# Sheet1.net
KiCad netlist of a schematic drawn in Altium Designer
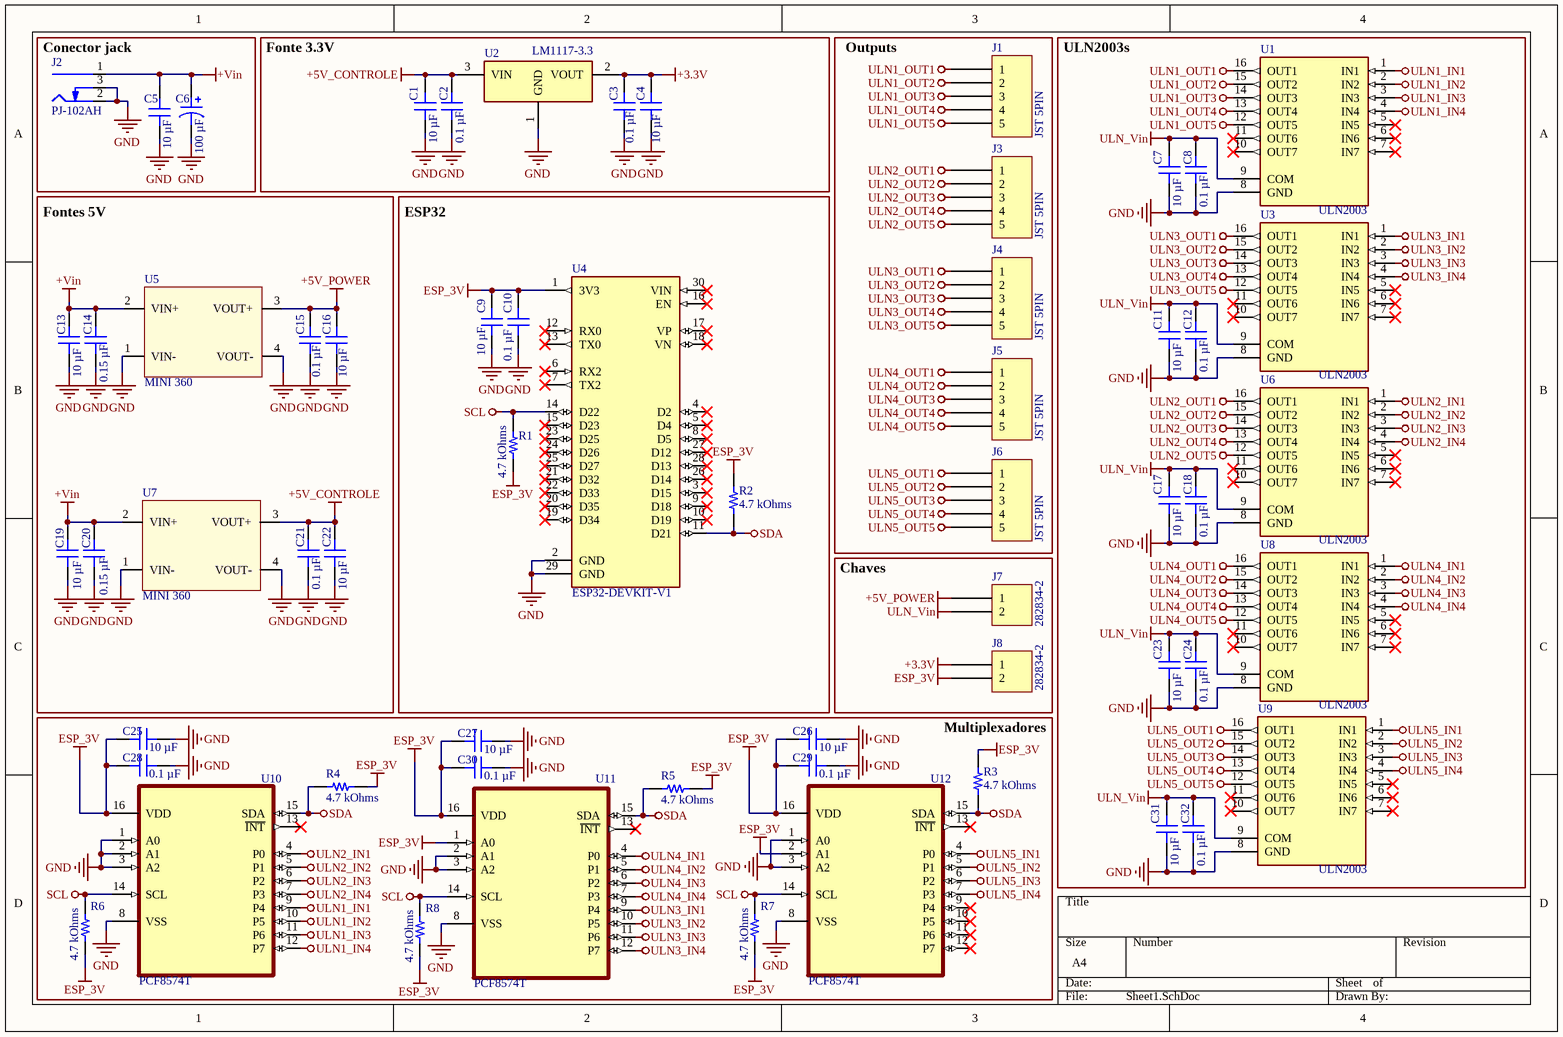
[diagram p0: Sheet1.SchDoc]

(export (version "E")
  (design (tool "Eeschema 10.0.6"))
  (components
    (comp (ref "C1")
      (value "10 µF")
      (footprint "CAP 0603_1608")
      (description "CAP CER 10UF 6.3V X5R 0603")
      (fields
        (field (name "PART NUMBER") "GRM188R60J106ME47D")
        (field (name "CAPACITANCE") "10 µF")
        (field (name "MANUFACTURER") "Murata Electronics")
      )
      (libsource (lib "Celestial Altium Library - altium_library") (part "Capacitor"))
    )
    (comp (ref "C2")
      (value "0.1 µF")
      (footprint "CAP 0603_1608")
      (description "CAP CER 0.1UF 6.3V X7R 0603")
      (fields
        (field (name "PART NUMBER") "6R3X14W104MV4T")
        (field (name "CAPACITANCE") "0.1 µF")
        (field (name "MANUFACTURER") "Johanson Dielectrics Inc.")
      )
      (libsource (lib "Celestial Altium Library - altium_library") (part "Capacitor"))
    )
    (comp (ref "C3")
      (value "0.1 µF")
      (footprint "CAP 0603_1608")
      (description "CAP CER 0.1UF 6.3V X7R 0603")
      (fields
        (field (name "PART NUMBER") "6R3X14W104MV4T")
        (field (name "CAPACITANCE") "0.1 µF")
        (field (name "MANUFACTURER") "Johanson Dielectrics Inc.")
      )
      (libsource (lib "Celestial Altium Library - altium_library") (part "Capacitor"))
    )
    (comp (ref "C4")
      (value "10 µF")
      (footprint "CAP 0603_1608")
      (description "CAP CER 10UF 6.3V X5R 0603")
      (fields
        (field (name "PART NUMBER") "GRM188R60J106ME47D")
        (field (name "CAPACITANCE") "10 µF")
        (field (name "MANUFACTURER") "Murata Electronics")
      )
      (libsource (lib "Celestial Altium Library - altium_library") (part "Capacitor"))
    )
    (comp (ref "C5")
      (value "10 µF")
      (footprint "CAP 1206_3216 - 0.8MM")
      (description "CAP CER 10UF 16V X5R 1206")
      (fields
        (field (name "PART NUMBER") "EMK316BJ106MD-T")
        (field (name "CAPACITANCE") "10 µF")
        (field (name "MANUFACTURER") "Taiyo Yuden")
      )
      (libsource (lib "Celestial Altium Library - altium_library") (part "Capacitor"))
    )
    (comp (ref "C6")
      (value "100 µF")
      (footprint "CAP AL TH D8 L3.5 H12.5")
      (description "CAP ALUM 100UF 20% 16V RADIAL")
      (fields (field (name "PART NUMBER") "UKL1C101MPD1TD") (field (name "MANUFACTURER") "Nichicon"))
      (libsource (lib "Celestial Altium Library - altium_library") (part "Polarised Capacitor"))
    )
    (comp (ref "C7")
      (value "10 µF")
      (footprint "CAP 0603_1608")
      (description "CAP CER 10UF 6.3V X5R 0603")
      (fields
        (field (name "PART NUMBER") "GRM188R60J106ME47D")
        (field (name "CAPACITANCE") "10 µF")
        (field (name "MANUFACTURER") "Murata Electronics")
      )
      (libsource (lib "Celestial Altium Library - altium_library") (part "Capacitor"))
    )
    (comp (ref "C8")
      (value "0.1 µF")
      (footprint "CAP 0603_1608")
      (description "CAP CER 0.1UF 6.3V X7R 0603")
      (fields
        (field (name "PART NUMBER") "6R3X14W104MV4T")
        (field (name "CAPACITANCE") "0.1 µF")
        (field (name "MANUFACTURER") "Johanson Dielectrics Inc.")
      )
      (libsource (lib "Celestial Altium Library - altium_library") (part "Capacitor"))
    )
    (comp (ref "C9")
      (value "10 µF")
      (footprint "CAP 0603_1608")
      (description "CAP CER 10UF 6.3V X5R 0603")
      (fields
        (field (name "PART NUMBER") "GRM188R60J106ME47D")
        (field (name "CAPACITANCE") "10 µF")
        (field (name "MANUFACTURER") "Murata Electronics")
      )
      (libsource (lib "Celestial Altium Library - altium_library") (part "Capacitor"))
    )
    (comp (ref "C10")
      (value "0.1 µF")
      (footprint "CAP 0603_1608")
      (description "CAP CER 0.1UF 6.3V X7R 0603")
      (fields
        (field (name "PART NUMBER") "6R3X14W104MV4T")
        (field (name "CAPACITANCE") "0.1 µF")
        (field (name "MANUFACTURER") "Johanson Dielectrics Inc.")
      )
      (libsource (lib "Celestial Altium Library - altium_library") (part "Capacitor"))
    )
    (comp (ref "C11")
      (value "10 µF")
      (footprint "CAP 0603_1608")
      (description "CAP CER 10UF 6.3V X5R 0603")
      (fields
        (field (name "PART NUMBER") "GRM188R60J106ME47D")
        (field (name "CAPACITANCE") "10 µF")
        (field (name "MANUFACTURER") "Murata Electronics")
      )
      (libsource (lib "Celestial Altium Library - altium_library") (part "Capacitor"))
    )
    (comp (ref "C12")
      (value "0.1 µF")
      (footprint "CAP 0603_1608")
      (description "CAP CER 0.1UF 6.3V X7R 0603")
      (fields
        (field (name "PART NUMBER") "6R3X14W104MV4T")
        (field (name "CAPACITANCE") "0.1 µF")
        (field (name "MANUFACTURER") "Johanson Dielectrics Inc.")
      )
      (libsource (lib "Celestial Altium Library - altium_library") (part "Capacitor"))
    )
    (comp (ref "C13")
      (value "10 µF")
      (footprint "CAP 1206_3216 - 0.8MM")
      (description "CAP CER 10UF 16V X5R 1206")
      (fields
        (field (name "PART NUMBER") "EMK316BJ106MD-T")
        (field (name "CAPACITANCE") "10 µF")
        (field (name "MANUFACTURER") "Taiyo Yuden")
      )
      (libsource (lib "Celestial Altium Library - altium_library") (part "Capacitor"))
    )
    (comp (ref "C14")
      (value "0.15 µF")
      (footprint "CAP 0805_2012")
      (description "CAP CER 0.15UF 50V X7R 0805")
      (fields
        (field (name "PART NUMBER") "C0805C154K5RACAUTO")
        (field (name "CAPACITANCE") "0.15 µF")
        (field (name "MANUFACTURER") "KEMET")
      )
      (libsource (lib "Celestial Altium Library - altium_library") (part "Capacitor"))
    )
    (comp (ref "C15")
      (value "0.1 µF")
      (footprint "CAP 0603_1608")
      (description "CAP CER 0.1UF 6.3V X7R 0603")
      (fields
        (field (name "PART NUMBER") "6R3X14W104MV4T")
        (field (name "CAPACITANCE") "0.1 µF")
        (field (name "MANUFACTURER") "Johanson Dielectrics Inc.")
      )
      (libsource (lib "Celestial Altium Library - altium_library") (part "Capacitor"))
    )
    (comp (ref "C16")
      (value "10 µF")
      (footprint "CAP 0603_1608")
      (description "CAP CER 10UF 6.3V X5R 0603")
      (fields
        (field (name "PART NUMBER") "GRM188R60J106ME47D")
        (field (name "CAPACITANCE") "10 µF")
        (field (name "MANUFACTURER") "Murata Electronics")
      )
      (libsource (lib "Celestial Altium Library - altium_library") (part "Capacitor"))
    )
    (comp (ref "C17")
      (value "10 µF")
      (footprint "CAP 0603_1608")
      (description "CAP CER 10UF 6.3V X5R 0603")
      (fields
        (field (name "PART NUMBER") "GRM188R60J106ME47D")
        (field (name "CAPACITANCE") "10 µF")
        (field (name "MANUFACTURER") "Murata Electronics")
      )
      (libsource (lib "Celestial Altium Library - altium_library") (part "Capacitor"))
    )
    (comp (ref "C18")
      (value "0.1 µF")
      (footprint "CAP 0603_1608")
      (description "CAP CER 0.1UF 6.3V X7R 0603")
      (fields
        (field (name "PART NUMBER") "6R3X14W104MV4T")
        (field (name "CAPACITANCE") "0.1 µF")
        (field (name "MANUFACTURER") "Johanson Dielectrics Inc.")
      )
      (libsource (lib "Celestial Altium Library - altium_library") (part "Capacitor"))
    )
    (comp (ref "C19")
      (value "10 µF")
      (footprint "CAP 1206_3216 - 0.8MM")
      (description "CAP CER 10UF 16V X5R 1206")
      (fields
        (field (name "PART NUMBER") "EMK316BJ106MD-T")
        (field (name "CAPACITANCE") "10 µF")
        (field (name "MANUFACTURER") "Taiyo Yuden")
      )
      (libsource (lib "Celestial Altium Library - altium_library") (part "Capacitor"))
    )
    (comp (ref "C20")
      (value "0.15 µF")
      (footprint "CAP 0805_2012")
      (description "CAP CER 0.15UF 50V X7R 0805")
      (fields
        (field (name "PART NUMBER") "C0805C154K5RACAUTO")
        (field (name "CAPACITANCE") "0.15 µF")
        (field (name "MANUFACTURER") "KEMET")
      )
      (libsource (lib "Celestial Altium Library - altium_library") (part "Capacitor"))
    )
    (comp (ref "C21")
      (value "0.1 µF")
      (footprint "CAP 0603_1608")
      (description "CAP CER 0.1UF 6.3V X7R 0603")
      (fields
        (field (name "PART NUMBER") "6R3X14W104MV4T")
        (field (name "CAPACITANCE") "0.1 µF")
        (field (name "MANUFACTURER") "Johanson Dielectrics Inc.")
      )
      (libsource (lib "Celestial Altium Library - altium_library") (part "Capacitor"))
    )
    (comp (ref "C22")
      (value "10 µF")
      (footprint "CAP 0603_1608")
      (description "CAP CER 10UF 6.3V X5R 0603")
      (fields
        (field (name "PART NUMBER") "GRM188R60J106ME47D")
        (field (name "CAPACITANCE") "10 µF")
        (field (name "MANUFACTURER") "Murata Electronics")
      )
      (libsource (lib "Celestial Altium Library - altium_library") (part "Capacitor"))
    )
    (comp (ref "C23")
      (value "10 µF")
      (footprint "CAP 0603_1608")
      (description "CAP CER 10UF 6.3V X5R 0603")
      (fields
        (field (name "PART NUMBER") "GRM188R60J106ME47D")
        (field (name "CAPACITANCE") "10 µF")
        (field (name "MANUFACTURER") "Murata Electronics")
      )
      (libsource (lib "Celestial Altium Library - altium_library") (part "Capacitor"))
    )
    (comp (ref "C24")
      (value "0.1 µF")
      (footprint "CAP 0603_1608")
      (description "CAP CER 0.1UF 6.3V X7R 0603")
      (fields
        (field (name "PART NUMBER") "6R3X14W104MV4T")
        (field (name "CAPACITANCE") "0.1 µF")
        (field (name "MANUFACTURER") "Johanson Dielectrics Inc.")
      )
      (libsource (lib "Celestial Altium Library - altium_library") (part "Capacitor"))
    )
    (comp (ref "C25")
      (value "10 µF")
      (footprint "CAP 0603_1608")
      (description "CAP CER 10UF 6.3V X5R 0603")
      (fields
        (field (name "PART NUMBER") "GRM188R60J106ME47D")
        (field (name "CAPACITANCE") "10 µF")
        (field (name "MANUFACTURER") "Murata Electronics")
      )
      (libsource (lib "Celestial Altium Library - altium_library") (part "Capacitor"))
    )
    (comp (ref "C26")
      (value "10 µF")
      (footprint "CAP 0603_1608")
      (description "CAP CER 10UF 6.3V X5R 0603")
      (fields
        (field (name "PART NUMBER") "GRM188R60J106ME47D")
        (field (name "CAPACITANCE") "10 µF")
        (field (name "MANUFACTURER") "Murata Electronics")
      )
      (libsource (lib "Celestial Altium Library - altium_library") (part "Capacitor"))
    )
    (comp (ref "C27")
      (value "10 µF")
      (footprint "CAP 0603_1608")
      (description "CAP CER 10UF 6.3V X5R 0603")
      (fields
        (field (name "PART NUMBER") "GRM188R60J106ME47D")
        (field (name "CAPACITANCE") "10 µF")
        (field (name "MANUFACTURER") "Murata Electronics")
      )
      (libsource (lib "Celestial Altium Library - altium_library") (part "Capacitor"))
    )
    (comp (ref "C28")
      (value "0.1 µF")
      (footprint "CAP 0603_1608")
      (description "CAP CER 0.1UF 6.3V X7R 0603")
      (fields
        (field (name "PART NUMBER") "6R3X14W104MV4T")
        (field (name "CAPACITANCE") "0.1 µF")
        (field (name "MANUFACTURER") "Johanson Dielectrics Inc.")
      )
      (libsource (lib "Celestial Altium Library - altium_library") (part "Capacitor"))
    )
    (comp (ref "C29")
      (value "0.1 µF")
      (footprint "CAP 0603_1608")
      (description "CAP CER 0.1UF 6.3V X7R 0603")
      (fields
        (field (name "PART NUMBER") "6R3X14W104MV4T")
        (field (name "CAPACITANCE") "0.1 µF")
        (field (name "MANUFACTURER") "Johanson Dielectrics Inc.")
      )
      (libsource (lib "Celestial Altium Library - altium_library") (part "Capacitor"))
    )
    (comp (ref "C30")
      (value "0.1 µF")
      (footprint "CAP 0603_1608")
      (description "CAP CER 0.1UF 6.3V X7R 0603")
      (fields
        (field (name "PART NUMBER") "6R3X14W104MV4T")
        (field (name "CAPACITANCE") "0.1 µF")
        (field (name "MANUFACTURER") "Johanson Dielectrics Inc.")
      )
      (libsource (lib "Celestial Altium Library - altium_library") (part "Capacitor"))
    )
    (comp (ref "C31")
      (value "10 µF")
      (footprint "CAP 0603_1608")
      (description "CAP CER 10UF 6.3V X5R 0603")
      (fields
        (field (name "PART NUMBER") "GRM188R60J106ME47D")
        (field (name "CAPACITANCE") "10 µF")
        (field (name "MANUFACTURER") "Murata Electronics")
      )
      (libsource (lib "Celestial Altium Library - altium_library") (part "Capacitor"))
    )
    (comp (ref "C32")
      (value "0.1 µF")
      (footprint "CAP 0603_1608")
      (description "CAP CER 0.1UF 6.3V X7R 0603")
      (fields
        (field (name "PART NUMBER") "6R3X14W104MV4T")
        (field (name "CAPACITANCE") "0.1 µF")
        (field (name "MANUFACTURER") "Johanson Dielectrics Inc.")
      )
      (libsource (lib "Celestial Altium Library - altium_library") (part "Capacitor"))
    )
    (comp (ref "J1")
      (value "JST 5PIN")
      (footprint "JST XH B5B-XH-A")
      (description "CONN HEADER VERT 5POS 2.5MM")
      (fields
        (field (name "PART NUMBER") "B5B-XH-A(LF)(SN)")
        (field (name "MANUFACTURER") "JST Sales America Inc.")
      )
      (libsource (lib "Celestial Altium Library - altium_library") (part "5 Pin"))
    )
    (comp (ref "J2")
      (value "PJ-102AH")
      (footprint "CUI PJ-102AH")
      (description "CONN PWR JACK 2X5.5MM SOLDER")
      (fields (field (name "MANUFACTURER") "CUI Devices"))
      (libsource (lib "Celestial Altium Library - altium_library") (part "Barrel Connector"))
    )
    (comp (ref "J3")
      (value "JST 5PIN")
      (footprint "JST XH B5B-XH-A")
      (description "CONN HEADER VERT 5POS 2.5MM")
      (fields
        (field (name "PART NUMBER") "B5B-XH-A(LF)(SN)")
        (field (name "MANUFACTURER") "JST Sales America Inc.")
      )
      (libsource (lib "Celestial Altium Library - altium_library") (part "5 Pin"))
    )
    (comp (ref "J4")
      (value "JST 5PIN")
      (footprint "JST XH B5B-XH-A")
      (description "CONN HEADER VERT 5POS 2.5MM")
      (fields
        (field (name "PART NUMBER") "B5B-XH-A(LF)(SN)")
        (field (name "MANUFACTURER") "JST Sales America Inc.")
      )
      (libsource (lib "Celestial Altium Library - altium_library") (part "5 Pin"))
    )
    (comp (ref "J5")
      (value "JST 5PIN")
      (footprint "JST XH B5B-XH-A")
      (description "CONN HEADER VERT 5POS 2.5MM")
      (fields
        (field (name "PART NUMBER") "B5B-XH-A(LF)(SN)")
        (field (name "MANUFACTURER") "JST Sales America Inc.")
      )
      (libsource (lib "Celestial Altium Library - altium_library") (part "5 Pin"))
    )
    (comp (ref "J6")
      (value "JST 5PIN")
      (footprint "JST XH B5B-XH-A")
      (description "CONN HEADER VERT 5POS 2.5MM")
      (fields
        (field (name "PART NUMBER") "B5B-XH-A(LF)(SN)")
        (field (name "MANUFACTURER") "JST Sales America Inc.")
      )
      (libsource (lib "Celestial Altium Library - altium_library") (part "5 Pin"))
    )
    (comp (ref "J7")
      (value "282834-2")
      (footprint "TE 282834-2")
      (description "TERM BLK 2P SIDE ENT 2.54MM PCB")
      (fields (field (name "MANUFACTURER") "TE Connectivity AMP Connectors") (field (name "VOLTAGE") "150V"))
      (libsource (lib "Celestial Altium Library - altium_library") (part "2 Pin"))
    )
    (comp (ref "J8")
      (value "282834-2")
      (footprint "TE 282834-2")
      (description "TERM BLK 2P SIDE ENT 2.54MM PCB")
      (fields (field (name "MANUFACTURER") "TE Connectivity AMP Connectors") (field (name "VOLTAGE") "150V"))
      (libsource (lib "Celestial Altium Library - altium_library") (part "2 Pin"))
    )
    (comp (ref "R1")
      (value "4.7 kOhms")
      (footprint "RES 0603_1608")
      (description "RES SMD 4.7K OHM 1% 1/10W 0603")
      (fields (field (name "PART NUMBER") "RT0603FRE074K7L") (field (name "MANUFACTURER") "Yageo"))
      (libsource (lib "Celestial Altium Library - altium_library") (part "Resistor"))
    )
    (comp (ref "R2")
      (value "4.7 kOhms")
      (footprint "RES 0603_1608")
      (description "RES SMD 4.7K OHM 1% 1/10W 0603")
      (fields (field (name "PART NUMBER") "RT0603FRE074K7L") (field (name "MANUFACTURER") "Yageo"))
      (libsource (lib "Celestial Altium Library - altium_library") (part "Resistor"))
    )
    (comp (ref "R3")
      (value "4.7 kOhms")
      (footprint "RES 0603_1608")
      (description "RES SMD 4.7K OHM 1% 1/10W 0603")
      (fields (field (name "PART NUMBER") "RT0603FRE074K7L") (field (name "MANUFACTURER") "Yageo"))
      (libsource (lib "Celestial Altium Library - altium_library") (part "Resistor"))
    )
    (comp (ref "R4")
      (value "4.7 kOhms")
      (footprint "RES 0603_1608")
      (description "RES SMD 4.7K OHM 1% 1/10W 0603")
      (fields (field (name "PART NUMBER") "RT0603FRE074K7L") (field (name "MANUFACTURER") "Yageo"))
      (libsource (lib "Celestial Altium Library - altium_library") (part "Resistor"))
    )
    (comp (ref "R5")
      (value "4.7 kOhms")
      (footprint "RES 0603_1608")
      (description "RES SMD 4.7K OHM 1% 1/10W 0603")
      (fields (field (name "PART NUMBER") "RT0603FRE074K7L") (field (name "MANUFACTURER") "Yageo"))
      (libsource (lib "Celestial Altium Library - altium_library") (part "Resistor"))
    )
    (comp (ref "R6")
      (value "4.7 kOhms")
      (footprint "RES 0603_1608")
      (description "RES SMD 4.7K OHM 1% 1/10W 0603")
      (fields (field (name "PART NUMBER") "RT0603FRE074K7L") (field (name "MANUFACTURER") "Yageo"))
      (libsource (lib "Celestial Altium Library - altium_library") (part "Resistor"))
    )
    (comp (ref "R7")
      (value "4.7 kOhms")
      (footprint "RES 0603_1608")
      (description "RES SMD 4.7K OHM 1% 1/10W 0603")
      (fields (field (name "PART NUMBER") "RT0603FRE074K7L") (field (name "MANUFACTURER") "Yageo"))
      (libsource (lib "Celestial Altium Library - altium_library") (part "Resistor"))
    )
    (comp (ref "R8")
      (value "4.7 kOhms")
      (footprint "RES 0603_1608")
      (description "RES SMD 4.7K OHM 1% 1/10W 0603")
      (fields (field (name "PART NUMBER") "RT0603FRE074K7L") (field (name "MANUFACTURER") "Yageo"))
      (libsource (lib "Celestial Altium Library - altium_library") (part "Resistor"))
    )
    (comp (ref "U1")
      (value "ULN2003")
      (footprint "DIP762W46P254L1969H533Q16")
      (description "Bipolar (BJT) Transistor Array 7 NPN Darlington 50V 500mA - - Surface Mount 16-SOIC")
      (fields (field (name "MF") "Texas Instruments"))
      (libsource (lib "ULN2003") (part "ULN2003"))
    )
    (comp (ref "U2")
      (value "LM1117-3.3")
      (footprint "SOT-223")
      (description "Linear Voltage Regulator IC Positive Fixed 1 Output 800mA DDPAK/TO-263-3")
      (fields (field (name "MF") "Texas Instruments"))
      (libsource (lib "LM1117-3.3") (part "LM1117-3.3"))
    )
    (comp (ref "U3")
      (value "ULN2003")
      (footprint "DIP762W46P254L1969H533Q16")
      (description "Bipolar (BJT) Transistor Array 7 NPN Darlington 50V 500mA - - Surface Mount 16-SOIC")
      (fields (field (name "MF") "Texas Instruments"))
      (libsource (lib "ULN2003") (part "ULN2003"))
    )
    (comp (ref "U4")
      (value "ESP32-DEVKIT-V1")
      (footprint "MODULE_ESP32_DEVKIT_V1")
      (fields (field (name "MF") "Do it"))
      (libsource (lib "ESP32-DEVKIT-V1") (part "ESP32-DEVKIT-V1"))
    )
    (comp (ref "U5")
      (value "MINI 360")
      (footprint "MINI360")
      (libsource (lib "bibliotecamini360") (part "MINI 360"))
    )
    (comp (ref "U6")
      (value "ULN2003")
      (footprint "DIP762W46P254L1969H533Q16")
      (description "Bipolar (BJT) Transistor Array 7 NPN Darlington 50V 500mA - - Surface Mount 16-SOIC")
      (fields (field (name "MF") "Texas Instruments"))
      (libsource (lib "ULN2003") (part "ULN2003"))
    )
    (comp (ref "U7")
      (value "MINI 360")
      (footprint "MINI360")
      (libsource (lib "bibliotecamini360") (part "MINI 360"))
    )
    (comp (ref "U8")
      (value "ULN2003")
      (footprint "DIP762W46P254L1969H533Q16")
      (description "Bipolar (BJT) Transistor Array 7 NPN Darlington 50V 500mA - - Surface Mount 16-SOIC")
      (fields (field (name "MF") "Texas Instruments"))
      (libsource (lib "ULN2003") (part "ULN2003"))
    )
    (comp (ref "U9")
      (value "ULN2003")
      (footprint "DIP762W46P254L1969H533Q16")
      (description "Bipolar (BJT) Transistor Array 7 NPN Darlington 50V 500mA - - Surface Mount 16-SOIC")
      (fields (field (name "MF") "Texas Instruments"))
      (libsource (lib "ULN2003") (part "ULN2003"))
    )
    (comp (ref "U10")
      (value "PCF8574T")
      (footprint "SOIC127P1032X265-16N")
      (description "I/O Expander 8 IÂ²C 100 kHz 20-SSOP")
      (fields (field (name "MF") "NXP Semiconductors"))
      (libsource (lib "PCF8574T") (part "PCF8574T"))
    )
    (comp (ref "U11")
      (value "PCF8574T")
      (footprint "SOIC127P1032X265-16N")
      (description "I/O Expander 8 IÂ²C 100 kHz 20-SSOP")
      (fields (field (name "MF") "NXP Semiconductors"))
      (libsource (lib "PCF8574T") (part "PCF8574T"))
    )
    (comp (ref "U12")
      (value "PCF8574T")
      (footprint "SOIC127P1032X265-16N")
      (description "I/O Expander 8 IÂ²C 100 kHz 20-SSOP")
      (fields (field (name "MF") "NXP Semiconductors"))
      (libsource (lib "PCF8574T") (part "PCF8574T"))
    )
  )
  (nets
    (net (code "1") (name "+3.3V") (class "Default")
      (node (ref "C3") (pin "1") (pinfunction "1_1") (pintype "passive"))
      (node (ref "C4") (pin "1") (pinfunction "1_1") (pintype "passive"))
      (node (ref "J8") (pin "1") (pinfunction "1_1") (pintype "passive"))
      (node (ref "U2") (pin "2") (pinfunction "VOUT_2") (pintype "passive"))
    )
    (net (code "2") (name "+5V_CONTROLE") (class "Default")
      (node (ref "C1") (pin "1") (pinfunction "1_1") (pintype "passive"))
      (node (ref "C2") (pin "1") (pinfunction "1_1") (pintype "passive"))
      (node (ref "C21") (pin "1") (pinfunction "1_1") (pintype "passive"))
      (node (ref "C22") (pin "1") (pinfunction "1_1") (pintype "passive"))
      (node (ref "U2") (pin "3") (pinfunction "VIN_3") (pintype "passive"))
      (node (ref "U7") (pin "3") (pinfunction "VOUT+_3") (pintype "passive"))
    )
    (net (code "3") (name "+5V_POWER") (class "Default")
      (node (ref "C15") (pin "1") (pinfunction "1_1") (pintype "passive"))
      (node (ref "C16") (pin "1") (pinfunction "1_1") (pintype "passive"))
      (node (ref "J7") (pin "1") (pinfunction "1_1") (pintype "passive"))
      (node (ref "U5") (pin "3") (pinfunction "VOUT+_3") (pintype "passive"))
    )
    (net (code "4") (name "+Vin") (class "Default")
      (node (ref "C13") (pin "1") (pinfunction "1_1") (pintype "passive"))
      (node (ref "C14") (pin "2") (pinfunction "2_2") (pintype "passive"))
      (node (ref "C19") (pin "1") (pinfunction "1_1") (pintype "passive"))
      (node (ref "C20") (pin "2") (pinfunction "2_2") (pintype "passive"))
      (node (ref "C5") (pin "1") (pinfunction "1_1") (pintype "passive"))
      (node (ref "C6") (pin "1") (pinfunction "1_1") (pintype "passive"))
      (node (ref "J2") (pin "1") (pinfunction "Centre_1") (pintype "passive"))
      (node (ref "U5") (pin "2") (pinfunction "VIN+_2") (pintype "passive"))
      (node (ref "U7") (pin "2") (pinfunction "VIN+_2") (pintype "passive"))
    )
    (net (code "5") (name "ESP_3V") (class "Default")
      (node (ref "C10") (pin "1") (pinfunction "1_1") (pintype "passive"))
      (node (ref "C25") (pin "1") (pinfunction "1_1") (pintype "passive"))
      (node (ref "C26") (pin "1") (pinfunction "1_1") (pintype "passive"))
      (node (ref "C27") (pin "1") (pinfunction "1_1") (pintype "passive"))
      (node (ref "C28") (pin "1") (pinfunction "1_1") (pintype "passive"))
      (node (ref "C29") (pin "1") (pinfunction "1_1") (pintype "passive"))
      (node (ref "C30") (pin "1") (pinfunction "1_1") (pintype "passive"))
      (node (ref "C9") (pin "1") (pinfunction "1_1") (pintype "passive"))
      (node (ref "J8") (pin "2") (pinfunction "2_2") (pintype "passive"))
      (node (ref "R1") (pin "2") (pinfunction "2_2") (pintype "passive"))
      (node (ref "R2") (pin "2") (pinfunction "2_2") (pintype "passive"))
      (node (ref "R3") (pin "2") (pinfunction "2_2") (pintype "passive"))
      (node (ref "R4") (pin "2") (pinfunction "2_2") (pintype "passive"))
      (node (ref "R5") (pin "2") (pinfunction "2_2") (pintype "passive"))
      (node (ref "R6") (pin "2") (pinfunction "2_2") (pintype "passive"))
      (node (ref "R7") (pin "2") (pinfunction "2_2") (pintype "passive"))
      (node (ref "R8") (pin "2") (pinfunction "2_2") (pintype "passive"))
      (node (ref "U10") (pin "16") (pinfunction "VDD_16") (pintype "power_in"))
      (node (ref "U11") (pin "1") (pinfunction "A0_1") (pintype "input"))
      (node (ref "U11") (pin "16") (pinfunction "VDD_16") (pintype "power_in"))
      (node (ref "U12") (pin "16") (pinfunction "VDD_16") (pintype "power_in"))
      (node (ref "U12") (pin "2") (pinfunction "A1_2") (pintype "input"))
      (node (ref "U4") (pin "1") (pinfunction "3V3_1") (pintype "output"))
    )
    (net (code "6") (name "GND") (class "Default")
      (node (ref "C1") (pin "2") (pinfunction "2_2") (pintype "passive"))
      (node (ref "C10") (pin "2") (pinfunction "2_2") (pintype "passive"))
      (node (ref "C11") (pin "2") (pinfunction "2_2") (pintype "passive"))
      (node (ref "C12") (pin "2") (pinfunction "2_2") (pintype "passive"))
      (node (ref "C13") (pin "2") (pinfunction "2_2") (pintype "passive"))
      (node (ref "C14") (pin "1") (pinfunction "1_1") (pintype "passive"))
      (node (ref "C15") (pin "2") (pinfunction "2_2") (pintype "passive"))
      (node (ref "C16") (pin "2") (pinfunction "2_2") (pintype "passive"))
      (node (ref "C17") (pin "2") (pinfunction "2_2") (pintype "passive"))
      (node (ref "C18") (pin "2") (pinfunction "2_2") (pintype "passive"))
      (node (ref "C19") (pin "2") (pinfunction "2_2") (pintype "passive"))
      (node (ref "C2") (pin "2") (pinfunction "2_2") (pintype "passive"))
      (node (ref "C20") (pin "1") (pinfunction "1_1") (pintype "passive"))
      (node (ref "C21") (pin "2") (pinfunction "2_2") (pintype "passive"))
      (node (ref "C22") (pin "2") (pinfunction "2_2") (pintype "passive"))
      (node (ref "C23") (pin "2") (pinfunction "2_2") (pintype "passive"))
      (node (ref "C24") (pin "2") (pinfunction "2_2") (pintype "passive"))
      (node (ref "C25") (pin "2") (pinfunction "2_2") (pintype "passive"))
      (node (ref "C26") (pin "2") (pinfunction "2_2") (pintype "passive"))
      (node (ref "C27") (pin "2") (pinfunction "2_2") (pintype "passive"))
      (node (ref "C28") (pin "2") (pinfunction "2_2") (pintype "passive"))
      (node (ref "C29") (pin "2") (pinfunction "2_2") (pintype "passive"))
      (node (ref "C3") (pin "2") (pinfunction "2_2") (pintype "passive"))
      (node (ref "C30") (pin "2") (pinfunction "2_2") (pintype "passive"))
      (node (ref "C31") (pin "2") (pinfunction "2_2") (pintype "passive"))
      (node (ref "C32") (pin "2") (pinfunction "2_2") (pintype "passive"))
      (node (ref "C4") (pin "2") (pinfunction "2_2") (pintype "passive"))
      (node (ref "C5") (pin "2") (pinfunction "2_2") (pintype "passive"))
      (node (ref "C6") (pin "2") (pinfunction "2_2") (pintype "passive"))
      (node (ref "C7") (pin "2") (pinfunction "2_2") (pintype "passive"))
      (node (ref "C8") (pin "2") (pinfunction "2_2") (pintype "passive"))
      (node (ref "C9") (pin "2") (pinfunction "2_2") (pintype "passive"))
      (node (ref "J2") (pin "2") (pinfunction "Outer_2") (pintype "passive"))
      (node (ref "J2") (pin "3") (pinfunction "SW_3") (pintype "passive"))
      (node (ref "U1") (pin "8") (pinfunction "GND_8") (pintype "power_in"))
      (node (ref "U10") (pin "1") (pinfunction "A0_1") (pintype "input"))
      (node (ref "U10") (pin "2") (pinfunction "A1_2") (pintype "input"))
      (node (ref "U10") (pin "3") (pinfunction "A2_3") (pintype "input"))
      (node (ref "U10") (pin "8") (pinfunction "VSS_8") (pintype "passive"))
      (node (ref "U11") (pin "2") (pinfunction "A1_2") (pintype "input"))
      (node (ref "U11") (pin "3") (pinfunction "A2_3") (pintype "input"))
      (node (ref "U11") (pin "8") (pinfunction "VSS_8") (pintype "passive"))
      (node (ref "U12") (pin "1") (pinfunction "A0_1") (pintype "input"))
      (node (ref "U12") (pin "3") (pinfunction "A2_3") (pintype "input"))
      (node (ref "U12") (pin "8") (pinfunction "VSS_8") (pintype "passive"))
      (node (ref "U2") (pin "1") (pinfunction "GND_1") (pintype "passive"))
      (node (ref "U3") (pin "8") (pinfunction "GND_8") (pintype "power_in"))
      (node (ref "U4") (pin "2") (pinfunction "GND_2") (pintype "power_in"))
      (node (ref "U4") (pin "29") (pinfunction "GND_29") (pintype "power_in"))
      (node (ref "U5") (pin "1") (pinfunction "VIN-_1") (pintype "passive"))
      (node (ref "U5") (pin "4") (pinfunction "VOUT-_4") (pintype "passive"))
      (node (ref "U6") (pin "8") (pinfunction "GND_8") (pintype "power_in"))
      (node (ref "U7") (pin "1") (pinfunction "VIN-_1") (pintype "passive"))
      (node (ref "U7") (pin "4") (pinfunction "VOUT-_4") (pintype "passive"))
      (node (ref "U8") (pin "8") (pinfunction "GND_8") (pintype "power_in"))
      (node (ref "U9") (pin "8") (pinfunction "GND_8") (pintype "power_in"))
    )
    (net (code "7") (name "SCL") (class "Default")
      (node (ref "R1") (pin "1") (pinfunction "1_1") (pintype "passive"))
      (node (ref "R6") (pin "1") (pinfunction "1_1") (pintype "passive"))
      (node (ref "R7") (pin "1") (pinfunction "1_1") (pintype "passive"))
      (node (ref "R8") (pin "1") (pinfunction "1_1") (pintype "passive"))
      (node (ref "U10") (pin "14") (pinfunction "SCL_14") (pintype "input"))
      (node (ref "U11") (pin "14") (pinfunction "SCL_14") (pintype "input"))
      (node (ref "U12") (pin "14") (pinfunction "SCL_14") (pintype "input"))
      (node (ref "U4") (pin "14") (pinfunction "D22_14") (pintype "bidirectional"))
    )
    (net (code "8") (name "SDA") (class "Default")
      (node (ref "R2") (pin "1") (pinfunction "1_1") (pintype "passive"))
      (node (ref "R3") (pin "1") (pinfunction "1_1") (pintype "passive"))
      (node (ref "R4") (pin "1") (pinfunction "1_1") (pintype "passive"))
      (node (ref "R5") (pin "1") (pinfunction "1_1") (pintype "passive"))
      (node (ref "U10") (pin "15") (pinfunction "SDA_15") (pintype "bidirectional"))
      (node (ref "U11") (pin "15") (pinfunction "SDA_15") (pintype "bidirectional"))
      (node (ref "U12") (pin "15") (pinfunction "SDA_15") (pintype "bidirectional"))
      (node (ref "U4") (pin "11") (pinfunction "D21_11") (pintype "bidirectional"))
    )
    (net (code "9") (name "ULN1_IN1") (class "Default")
      (node (ref "U1") (pin "1") (pinfunction "IN1_1") (pintype "input"))
      (node (ref "U10") (pin "9") (pinfunction "P4_9") (pintype "bidirectional"))
    )
    (net (code "10") (name "ULN1_IN2") (class "Default")
      (node (ref "U1") (pin "2") (pinfunction "IN2_2") (pintype "input"))
      (node (ref "U10") (pin "10") (pinfunction "P5_10") (pintype "bidirectional"))
    )
    (net (code "11") (name "ULN1_IN3") (class "Default")
      (node (ref "U1") (pin "3") (pinfunction "IN3_3") (pintype "input"))
      (node (ref "U10") (pin "11") (pinfunction "P6_11") (pintype "bidirectional"))
    )
    (net (code "12") (name "ULN1_IN4") (class "Default")
      (node (ref "U1") (pin "4") (pinfunction "IN4_4") (pintype "input"))
      (node (ref "U10") (pin "12") (pinfunction "P7_12") (pintype "bidirectional"))
    )
    (net (code "13") (name "ULN1_OUT1") (class "Default")
      (node (ref "J1") (pin "1") (pinfunction "1_1") (pintype "passive"))
      (node (ref "U1") (pin "16") (pinfunction "OUT1_16") (pintype "output"))
    )
    (net (code "14") (name "ULN1_OUT2") (class "Default")
      (node (ref "J1") (pin "2") (pinfunction "2_2") (pintype "passive"))
      (node (ref "U1") (pin "15") (pinfunction "OUT2_15") (pintype "output"))
    )
    (net (code "15") (name "ULN1_OUT3") (class "Default")
      (node (ref "J1") (pin "3") (pinfunction "3_3") (pintype "passive"))
      (node (ref "U1") (pin "14") (pinfunction "OUT3_14") (pintype "output"))
    )
    (net (code "16") (name "ULN1_OUT4") (class "Default")
      (node (ref "J1") (pin "4") (pinfunction "4_4") (pintype "passive"))
      (node (ref "U1") (pin "13") (pinfunction "OUT4_13") (pintype "output"))
    )
    (net (code "17") (name "ULN1_OUT5") (class "Default")
      (node (ref "J1") (pin "5") (pinfunction "5_5") (pintype "passive"))
      (node (ref "U1") (pin "12") (pinfunction "OUT5_12") (pintype "output"))
    )
    (net (code "18") (name "ULN2_IN1") (class "Default")
      (node (ref "U10") (pin "4") (pinfunction "P0_4") (pintype "bidirectional"))
      (node (ref "U6") (pin "1") (pinfunction "IN1_1") (pintype "input"))
    )
    (net (code "19") (name "ULN2_IN2") (class "Default")
      (node (ref "U10") (pin "5") (pinfunction "P1_5") (pintype "bidirectional"))
      (node (ref "U6") (pin "2") (pinfunction "IN2_2") (pintype "input"))
    )
    (net (code "20") (name "ULN2_IN3") (class "Default")
      (node (ref "U10") (pin "6") (pinfunction "P2_6") (pintype "bidirectional"))
      (node (ref "U6") (pin "3") (pinfunction "IN3_3") (pintype "input"))
    )
    (net (code "21") (name "ULN2_IN4") (class "Default")
      (node (ref "U10") (pin "7") (pinfunction "P3_7") (pintype "bidirectional"))
      (node (ref "U6") (pin "4") (pinfunction "IN4_4") (pintype "input"))
    )
    (net (code "22") (name "ULN2_OUT1") (class "Default")
      (node (ref "J3") (pin "1") (pinfunction "1_1") (pintype "passive"))
      (node (ref "U6") (pin "16") (pinfunction "OUT1_16") (pintype "output"))
    )
    (net (code "23") (name "ULN2_OUT2") (class "Default")
      (node (ref "J3") (pin "2") (pinfunction "2_2") (pintype "passive"))
      (node (ref "U6") (pin "15") (pinfunction "OUT2_15") (pintype "output"))
    )
    (net (code "24") (name "ULN2_OUT3") (class "Default")
      (node (ref "J3") (pin "3") (pinfunction "3_3") (pintype "passive"))
      (node (ref "U6") (pin "14") (pinfunction "OUT3_14") (pintype "output"))
    )
    (net (code "25") (name "ULN2_OUT4") (class "Default")
      (node (ref "J3") (pin "4") (pinfunction "4_4") (pintype "passive"))
      (node (ref "U6") (pin "13") (pinfunction "OUT4_13") (pintype "output"))
    )
    (net (code "26") (name "ULN2_OUT5") (class "Default")
      (node (ref "J3") (pin "5") (pinfunction "5_5") (pintype "passive"))
      (node (ref "U6") (pin "12") (pinfunction "OUT5_12") (pintype "output"))
    )
    (net (code "27") (name "ULN3_IN1") (class "Default")
      (node (ref "U11") (pin "9") (pinfunction "P4_9") (pintype "bidirectional"))
      (node (ref "U3") (pin "1") (pinfunction "IN1_1") (pintype "input"))
    )
    (net (code "28") (name "ULN3_IN2") (class "Default")
      (node (ref "U11") (pin "10") (pinfunction "P5_10") (pintype "bidirectional"))
      (node (ref "U3") (pin "2") (pinfunction "IN2_2") (pintype "input"))
    )
    (net (code "29") (name "ULN3_IN3") (class "Default")
      (node (ref "U11") (pin "11") (pinfunction "P6_11") (pintype "bidirectional"))
      (node (ref "U3") (pin "3") (pinfunction "IN3_3") (pintype "input"))
    )
    (net (code "30") (name "ULN3_IN4") (class "Default")
      (node (ref "U11") (pin "12") (pinfunction "P7_12") (pintype "bidirectional"))
      (node (ref "U3") (pin "4") (pinfunction "IN4_4") (pintype "input"))
    )
    (net (code "31") (name "ULN3_OUT1") (class "Default")
      (node (ref "J4") (pin "1") (pinfunction "1_1") (pintype "passive"))
      (node (ref "U3") (pin "16") (pinfunction "OUT1_16") (pintype "output"))
    )
    (net (code "32") (name "ULN3_OUT2") (class "Default")
      (node (ref "J4") (pin "2") (pinfunction "2_2") (pintype "passive"))
      (node (ref "U3") (pin "15") (pinfunction "OUT2_15") (pintype "output"))
    )
    (net (code "33") (name "ULN3_OUT3") (class "Default")
      (node (ref "J4") (pin "3") (pinfunction "3_3") (pintype "passive"))
      (node (ref "U3") (pin "14") (pinfunction "OUT3_14") (pintype "output"))
    )
    (net (code "34") (name "ULN3_OUT4") (class "Default")
      (node (ref "J4") (pin "4") (pinfunction "4_4") (pintype "passive"))
      (node (ref "U3") (pin "13") (pinfunction "OUT4_13") (pintype "output"))
    )
    (net (code "35") (name "ULN3_OUT5") (class "Default")
      (node (ref "J4") (pin "5") (pinfunction "5_5") (pintype "passive"))
      (node (ref "U3") (pin "12") (pinfunction "OUT5_12") (pintype "output"))
    )
    (net (code "36") (name "ULN4_IN1") (class "Default")
      (node (ref "U11") (pin "4") (pinfunction "P0_4") (pintype "bidirectional"))
      (node (ref "U8") (pin "1") (pinfunction "IN1_1") (pintype "input"))
    )
    (net (code "37") (name "ULN4_IN2") (class "Default")
      (node (ref "U11") (pin "5") (pinfunction "P1_5") (pintype "bidirectional"))
      (node (ref "U8") (pin "2") (pinfunction "IN2_2") (pintype "input"))
    )
    (net (code "38") (name "ULN4_IN3") (class "Default")
      (node (ref "U11") (pin "6") (pinfunction "P2_6") (pintype "bidirectional"))
      (node (ref "U8") (pin "3") (pinfunction "IN3_3") (pintype "input"))
    )
    (net (code "39") (name "ULN4_IN4") (class "Default")
      (node (ref "U11") (pin "7") (pinfunction "P3_7") (pintype "bidirectional"))
      (node (ref "U8") (pin "4") (pinfunction "IN4_4") (pintype "input"))
    )
    (net (code "40") (name "ULN4_OUT1") (class "Default")
      (node (ref "J5") (pin "1") (pinfunction "1_1") (pintype "passive"))
      (node (ref "U8") (pin "16") (pinfunction "OUT1_16") (pintype "output"))
    )
    (net (code "41") (name "ULN4_OUT2") (class "Default")
      (node (ref "J5") (pin "2") (pinfunction "2_2") (pintype "passive"))
      (node (ref "U8") (pin "15") (pinfunction "OUT2_15") (pintype "output"))
    )
    (net (code "42") (name "ULN4_OUT3") (class "Default")
      (node (ref "J5") (pin "3") (pinfunction "3_3") (pintype "passive"))
      (node (ref "U8") (pin "14") (pinfunction "OUT3_14") (pintype "output"))
    )
    (net (code "43") (name "ULN4_OUT4") (class "Default")
      (node (ref "J5") (pin "4") (pinfunction "4_4") (pintype "passive"))
      (node (ref "U8") (pin "13") (pinfunction "OUT4_13") (pintype "output"))
    )
    (net (code "44") (name "ULN4_OUT5") (class "Default")
      (node (ref "J5") (pin "5") (pinfunction "5_5") (pintype "passive"))
      (node (ref "U8") (pin "12") (pinfunction "OUT5_12") (pintype "output"))
    )
    (net (code "45") (name "ULN5_IN1") (class "Default")
      (node (ref "U12") (pin "4") (pinfunction "P0_4") (pintype "bidirectional"))
      (node (ref "U9") (pin "1") (pinfunction "IN1_1") (pintype "input"))
    )
    (net (code "46") (name "ULN5_IN2") (class "Default")
      (node (ref "U12") (pin "5") (pinfunction "P1_5") (pintype "bidirectional"))
      (node (ref "U9") (pin "2") (pinfunction "IN2_2") (pintype "input"))
    )
    (net (code "47") (name "ULN5_IN3") (class "Default")
      (node (ref "U12") (pin "6") (pinfunction "P2_6") (pintype "bidirectional"))
      (node (ref "U9") (pin "3") (pinfunction "IN3_3") (pintype "input"))
    )
    (net (code "48") (name "ULN5_IN4") (class "Default")
      (node (ref "U12") (pin "7") (pinfunction "P3_7") (pintype "bidirectional"))
      (node (ref "U9") (pin "4") (pinfunction "IN4_4") (pintype "input"))
    )
    (net (code "49") (name "ULN5_OUT1") (class "Default")
      (node (ref "J6") (pin "1") (pinfunction "1_1") (pintype "passive"))
      (node (ref "U9") (pin "16") (pinfunction "OUT1_16") (pintype "output"))
    )
    (net (code "50") (name "ULN5_OUT2") (class "Default")
      (node (ref "J6") (pin "2") (pinfunction "2_2") (pintype "passive"))
      (node (ref "U9") (pin "15") (pinfunction "OUT2_15") (pintype "output"))
    )
    (net (code "51") (name "ULN5_OUT3") (class "Default")
      (node (ref "J6") (pin "3") (pinfunction "3_3") (pintype "passive"))
      (node (ref "U9") (pin "14") (pinfunction "OUT3_14") (pintype "output"))
    )
    (net (code "52") (name "ULN5_OUT4") (class "Default")
      (node (ref "J6") (pin "4") (pinfunction "4_4") (pintype "passive"))
      (node (ref "U9") (pin "13") (pinfunction "OUT4_13") (pintype "output"))
    )
    (net (code "53") (name "ULN5_OUT5") (class "Default")
      (node (ref "J6") (pin "5") (pinfunction "5_5") (pintype "passive"))
      (node (ref "U9") (pin "12") (pinfunction "OUT5_12") (pintype "output"))
    )
    (net (code "54") (name "ULN_Vin") (class "Default")
      (node (ref "C11") (pin "1") (pinfunction "1_1") (pintype "passive"))
      (node (ref "C12") (pin "1") (pinfunction "1_1") (pintype "passive"))
      (node (ref "C17") (pin "1") (pinfunction "1_1") (pintype "passive"))
      (node (ref "C18") (pin "1") (pinfunction "1_1") (pintype "passive"))
      (node (ref "C23") (pin "1") (pinfunction "1_1") (pintype "passive"))
      (node (ref "C24") (pin "1") (pinfunction "1_1") (pintype "passive"))
      (node (ref "C31") (pin "1") (pinfunction "1_1") (pintype "passive"))
      (node (ref "C32") (pin "1") (pinfunction "1_1") (pintype "passive"))
      (node (ref "C7") (pin "1") (pinfunction "1_1") (pintype "passive"))
      (node (ref "C8") (pin "1") (pinfunction "1_1") (pintype "passive"))
      (node (ref "J7") (pin "2") (pinfunction "2_2") (pintype "passive"))
      (node (ref "U1") (pin "9") (pinfunction "COM_9") (pintype "power_in"))
      (node (ref "U3") (pin "9") (pinfunction "COM_9") (pintype "power_in"))
      (node (ref "U6") (pin "9") (pinfunction "COM_9") (pintype "power_in"))
      (node (ref "U8") (pin "9") (pinfunction "COM_9") (pintype "power_in"))
      (node (ref "U9") (pin "9") (pinfunction "COM_9") (pintype "power_in"))
    )
    (net (code "55") (name "unconnected-(U1-IN5-Pad5)") (class "Default")
      (node (ref "U1") (pin "5") (pinfunction "IN5_5") (pintype "input+no_connect"))
    )
    (net (code "56") (name "unconnected-(U1-IN6-Pad6)") (class "Default")
      (node (ref "U1") (pin "6") (pinfunction "IN6_6") (pintype "input+no_connect"))
    )
    (net (code "57") (name "unconnected-(U1-IN7-Pad7)") (class "Default")
      (node (ref "U1") (pin "7") (pinfunction "IN7_7") (pintype "input+no_connect"))
    )
    (net (code "58") (name "unconnected-(U1-OUT6-Pad11)") (class "Default")
      (node (ref "U1") (pin "11") (pinfunction "OUT6_11") (pintype "output+no_connect"))
    )
    (net (code "59") (name "unconnected-(U1-OUT7-Pad10)") (class "Default")
      (node (ref "U1") (pin "10") (pinfunction "OUT7_10") (pintype "output+no_connect"))
    )
    (net (code "60") (name "unconnected-(U3-IN5-Pad5)") (class "Default")
      (node (ref "U3") (pin "5") (pinfunction "IN5_5") (pintype "input+no_connect"))
    )
    (net (code "61") (name "unconnected-(U3-IN6-Pad6)") (class "Default")
      (node (ref "U3") (pin "6") (pinfunction "IN6_6") (pintype "input+no_connect"))
    )
    (net (code "62") (name "unconnected-(U3-IN7-Pad7)") (class "Default")
      (node (ref "U3") (pin "7") (pinfunction "IN7_7") (pintype "input+no_connect"))
    )
    (net (code "63") (name "unconnected-(U3-OUT6-Pad11)") (class "Default")
      (node (ref "U3") (pin "11") (pinfunction "OUT6_11") (pintype "output+no_connect"))
    )
    (net (code "64") (name "unconnected-(U3-OUT7-Pad10)") (class "Default")
      (node (ref "U3") (pin "10") (pinfunction "OUT7_10") (pintype "output+no_connect"))
    )
    (net (code "65") (name "unconnected-(U4-D2-Pad4)") (class "Default")
      (node (ref "U4") (pin "4") (pinfunction "D2_4") (pintype "bidirectional+no_connect"))
    )
    (net (code "66") (name "unconnected-(U4-D4-Pad5)") (class "Default")
      (node (ref "U4") (pin "5") (pinfunction "D4_5") (pintype "bidirectional+no_connect"))
    )
    (net (code "67") (name "unconnected-(U4-D5-Pad8)") (class "Default")
      (node (ref "U4") (pin "8") (pinfunction "D5_8") (pintype "bidirectional+no_connect"))
    )
    (net (code "68") (name "unconnected-(U4-D12-Pad27)") (class "Default")
      (node (ref "U4") (pin "27") (pinfunction "D12_27") (pintype "bidirectional+no_connect"))
    )
    (net (code "69") (name "unconnected-(U4-D13-Pad28)") (class "Default")
      (node (ref "U4") (pin "28") (pinfunction "D13_28") (pintype "bidirectional+no_connect"))
    )
    (net (code "70") (name "unconnected-(U4-D14-Pad26)") (class "Default")
      (node (ref "U4") (pin "26") (pinfunction "D14_26") (pintype "bidirectional+no_connect"))
    )
    (net (code "71") (name "unconnected-(U4-D15-Pad3)") (class "Default")
      (node (ref "U4") (pin "3") (pinfunction "D15_3") (pintype "bidirectional+no_connect"))
    )
    (net (code "72") (name "unconnected-(U4-D18-Pad9)") (class "Default")
      (node (ref "U4") (pin "9") (pinfunction "D18_9") (pintype "bidirectional+no_connect"))
    )
    (net (code "73") (name "unconnected-(U4-D19-Pad10)") (class "Default")
      (node (ref "U4") (pin "10") (pinfunction "D19_10") (pintype "bidirectional+no_connect"))
    )
    (net (code "74") (name "unconnected-(U4-D23-Pad15)") (class "Default")
      (node (ref "U4") (pin "15") (pinfunction "D23_15") (pintype "bidirectional+no_connect"))
    )
    (net (code "75") (name "unconnected-(U4-D25-Pad23)") (class "Default")
      (node (ref "U4") (pin "23") (pinfunction "D25_23") (pintype "bidirectional+no_connect"))
    )
    (net (code "76") (name "unconnected-(U4-D26-Pad24)") (class "Default")
      (node (ref "U4") (pin "24") (pinfunction "D26_24") (pintype "bidirectional+no_connect"))
    )
    (net (code "77") (name "unconnected-(U4-D27-Pad25)") (class "Default")
      (node (ref "U4") (pin "25") (pinfunction "D27_25") (pintype "bidirectional+no_connect"))
    )
    (net (code "78") (name "unconnected-(U4-D32-Pad21)") (class "Default")
      (node (ref "U4") (pin "21") (pinfunction "D32_21") (pintype "bidirectional+no_connect"))
    )
    (net (code "79") (name "unconnected-(U4-D33-Pad22)") (class "Default")
      (node (ref "U4") (pin "22") (pinfunction "D33_22") (pintype "bidirectional+no_connect"))
    )
    (net (code "80") (name "unconnected-(U4-D34-Pad19)") (class "Default")
      (node (ref "U4") (pin "19") (pinfunction "D34_19") (pintype "bidirectional+no_connect"))
    )
    (net (code "81") (name "unconnected-(U4-D35-Pad20)") (class "Default")
      (node (ref "U4") (pin "20") (pinfunction "D35_20") (pintype "bidirectional+no_connect"))
    )
    (net (code "82") (name "unconnected-(U4-EN-Pad16)") (class "Default")
      (node (ref "U4") (pin "16") (pinfunction "EN_16") (pintype "input+no_connect"))
    )
    (net (code "83") (name "unconnected-(U4-RX0-Pad12)") (class "Default")
      (node (ref "U4") (pin "12") (pinfunction "RX0_12") (pintype "input+no_connect"))
    )
    (net (code "84") (name "unconnected-(U4-RX2-Pad6)") (class "Default")
      (node (ref "U4") (pin "6") (pinfunction "RX2_6") (pintype "input+no_connect"))
    )
    (net (code "85") (name "unconnected-(U4-TX0-Pad13)") (class "Default")
      (node (ref "U4") (pin "13") (pinfunction "TX0_13") (pintype "output+no_connect"))
    )
    (net (code "86") (name "unconnected-(U4-TX2-Pad7)") (class "Default")
      (node (ref "U4") (pin "7") (pinfunction "TX2_7") (pintype "output+no_connect"))
    )
    (net (code "87") (name "unconnected-(U4-VIN-Pad30)") (class "Default")
      (node (ref "U4") (pin "30") (pinfunction "VIN_30") (pintype "input+no_connect"))
    )
    (net (code "88") (name "unconnected-(U4-VN-Pad18)") (class "Default")
      (node (ref "U4") (pin "18") (pinfunction "VN_18") (pintype "bidirectional+no_connect"))
    )
    (net (code "89") (name "unconnected-(U4-VP-Pad17)") (class "Default")
      (node (ref "U4") (pin "17") (pinfunction "VP_17") (pintype "bidirectional+no_connect"))
    )
    (net (code "90") (name "unconnected-(U6-IN5-Pad5)") (class "Default")
      (node (ref "U6") (pin "5") (pinfunction "IN5_5") (pintype "input+no_connect"))
    )
    (net (code "91") (name "unconnected-(U6-IN6-Pad6)") (class "Default")
      (node (ref "U6") (pin "6") (pinfunction "IN6_6") (pintype "input+no_connect"))
    )
    (net (code "92") (name "unconnected-(U6-IN7-Pad7)") (class "Default")
      (node (ref "U6") (pin "7") (pinfunction "IN7_7") (pintype "input+no_connect"))
    )
    (net (code "93") (name "unconnected-(U6-OUT6-Pad11)") (class "Default")
      (node (ref "U6") (pin "11") (pinfunction "OUT6_11") (pintype "output+no_connect"))
    )
    (net (code "94") (name "unconnected-(U6-OUT7-Pad10)") (class "Default")
      (node (ref "U6") (pin "10") (pinfunction "OUT7_10") (pintype "output+no_connect"))
    )
    (net (code "95") (name "unconnected-(U8-IN5-Pad5)") (class "Default")
      (node (ref "U8") (pin "5") (pinfunction "IN5_5") (pintype "input+no_connect"))
    )
    (net (code "96") (name "unconnected-(U8-IN6-Pad6)") (class "Default")
      (node (ref "U8") (pin "6") (pinfunction "IN6_6") (pintype "input+no_connect"))
    )
    (net (code "97") (name "unconnected-(U8-IN7-Pad7)") (class "Default")
      (node (ref "U8") (pin "7") (pinfunction "IN7_7") (pintype "input+no_connect"))
    )
    (net (code "98") (name "unconnected-(U8-OUT6-Pad11)") (class "Default")
      (node (ref "U8") (pin "11") (pinfunction "OUT6_11") (pintype "output+no_connect"))
    )
    (net (code "99") (name "unconnected-(U8-OUT7-Pad10)") (class "Default")
      (node (ref "U8") (pin "10") (pinfunction "OUT7_10") (pintype "output+no_connect"))
    )
    (net (code "100") (name "unconnected-(U9-IN5-Pad5)") (class "Default")
      (node (ref "U9") (pin "5") (pinfunction "IN5_5") (pintype "input+no_connect"))
    )
    (net (code "101") (name "unconnected-(U9-IN6-Pad6)") (class "Default")
      (node (ref "U9") (pin "6") (pinfunction "IN6_6") (pintype "input+no_connect"))
    )
    (net (code "102") (name "unconnected-(U9-IN7-Pad7)") (class "Default")
      (node (ref "U9") (pin "7") (pinfunction "IN7_7") (pintype "input+no_connect"))
    )
    (net (code "103") (name "unconnected-(U9-OUT6-Pad11)") (class "Default")
      (node (ref "U9") (pin "11") (pinfunction "OUT6_11") (pintype "output+no_connect"))
    )
    (net (code "104") (name "unconnected-(U9-OUT7-Pad10)") (class "Default")
      (node (ref "U9") (pin "10") (pinfunction "OUT7_10") (pintype "output+no_connect"))
    )
    (net (code "105") (name "unconnected-(U10-~{INT}-Pad13)") (class "Default")
      (node (ref "U10") (pin "13") (pinfunction "~{INT}_13") (pintype "output+no_connect"))
    )
    (net (code "106") (name "unconnected-(U11-~{INT}-Pad13)") (class "Default")
      (node (ref "U11") (pin "13") (pinfunction "~{INT}_13") (pintype "output+no_connect"))
    )
    (net (code "107") (name "unconnected-(U12-P4-Pad9)") (class "Default")
      (node (ref "U12") (pin "9") (pinfunction "P4_9") (pintype "bidirectional+no_connect"))
    )
    (net (code "108") (name "unconnected-(U12-P5-Pad10)") (class "Default")
      (node (ref "U12") (pin "10") (pinfunction "P5_10") (pintype "bidirectional+no_connect"))
    )
    (net (code "109") (name "unconnected-(U12-P6-Pad11)") (class "Default")
      (node (ref "U12") (pin "11") (pinfunction "P6_11") (pintype "bidirectional+no_connect"))
    )
    (net (code "110") (name "unconnected-(U12-P7-Pad12)") (class "Default")
      (node (ref "U12") (pin "12") (pinfunction "P7_12") (pintype "bidirectional+no_connect"))
    )
    (net (code "111") (name "unconnected-(U12-~{INT}-Pad13)") (class "Default")
      (node (ref "U12") (pin "13") (pinfunction "~{INT}_13") (pintype "output+no_connect"))
    )
  )
)
